# XL6009.net
KiCad netlist of a schematic drawn in Altium Designer
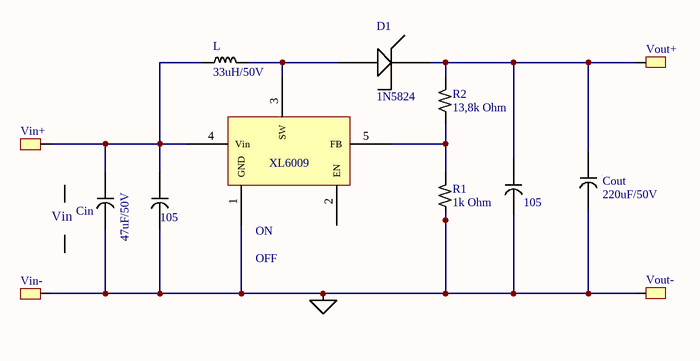
[diagram p0: XL6009.SchDoc]

(export (version "E")
  (design (tool "Eeschema 10.0.6"))
  (components
    (comp (ref "*") (value "Component_1") (libsource (lib "Schlib1") (part "Component_1")))
    (comp (ref "*1") (value "Component_2") (libsource (lib "Schlib1") (part "Component_2")))
    (comp (ref "*2") (value "Component_2") (libsource (lib "Schlib1") (part "Component_2")))
    (comp (ref "1") (value "105") (footprint "PCBComponent_1") (libsource (lib "Schlib1") (part "105")))
    (comp (ref "105") (value "105") (footprint "PCBComponent_1") (libsource (lib "Schlib1") (part "105")))
    (comp (ref "Cin")
      (value "47uF/50V")
      (footprint "Cout:PCBComponent_1")
      (libsource (lib "Schlib1") (part "capacitor"))
    )
    (comp (ref "Cout")
      (value "220uF/50V")
      (footprint "Cout:PCBComponent_1")
      (libsource (lib "Schlib1") (part "capacitor"))
    )
    (comp (ref "D1") (value "1N5824") (footprint "1N5824") (libsource (lib "Schlib1") (part "diode")))
    (comp (ref "L")
      (value "33uH/50V")
      (footprint "coil:PCBComponent_1")
      (libsource (lib "Schlib1") (part "Electrolytic Cap"))
    )
    (comp (ref "R1")
      (value "1k Ohm")
      (footprint "resistor0805:PCBComponent_1")
      (libsource (lib "Schlib1") (part "resistor"))
    )
    (comp (ref "R2")
      (value "13,8k Ohm")
      (footprint "resistor0805:PCBComponent_1")
      (libsource (lib "Schlib1") (part "resistor"))
    )
    (comp (ref "Vin+") (value "p1") (footprint "P1") (libsource (lib "Schlib1") (part "p1")))
    (comp (ref "Vin-") (value "p1") (footprint "P1") (libsource (lib "Schlib1") (part "p1")))
    (comp (ref "Vout+") (value "p1") (footprint "P1") (libsource (lib "") (part "p1_1")))
    (comp (ref "Vout-") (value "p1") (footprint "P1") (libsource (lib "") (part "p1_1")))
    (comp (ref "XL6009") (value "XL6009") (footprint "XL6009") (libsource (lib "Schlib1") (part "XL6009")))
  )
  (nets
    (net (code "1") (name "GND") (class "Default")
      (node (ref "1") (pin "2") (pinfunction "2_2") (pintype "passive"))
      (node (ref "105") (pin "2") (pinfunction "2_2") (pintype "passive"))
      (node (ref "Cin") (pin "2") (pinfunction "2_2") (pintype "passive"))
      (node (ref "Cout") (pin "2") (pinfunction "2_2") (pintype "passive"))
      (node (ref "R1") (pin "1") (pinfunction "1_1") (pintype "passive"))
      (node (ref "Vin-") (pin "21") (pinfunction "21_21") (pintype "passive"))
      (node (ref "Vout-") (pin "21") (pinfunction "21_21") (pintype "passive"))
      (node (ref "XL6009") (pin "1") (pinfunction "GND_1") (pintype "passive"))
    )
    (net (code "2") (name "Net-(1-Pad1)") (class "Default")
      (node (ref "1") (pin "1") (pinfunction "1_1") (pintype "passive"))
      (node (ref "Cout") (pin "1") (pinfunction "1_1") (pintype "passive"))
      (node (ref "D1") (pin "1") (pinfunction "1_1") (pintype "passive"))
      (node (ref "R2") (pin "2") (pinfunction "1_2") (pintype "passive"))
      (node (ref "Vout+") (pin "21") (pinfunction "21_21") (pintype "passive"))
    )
    (net (code "3") (name "Net-(XL6009-FB)") (class "Default")
      (node (ref "R1") (pin "2") (pinfunction "1_2") (pintype "passive"))
      (node (ref "R2") (pin "1") (pinfunction "1_1") (pintype "passive"))
      (node (ref "XL6009") (pin "5") (pinfunction "FB_5") (pintype "passive"))
    )
    (net (code "4") (name "Net-(XL6009-SW)") (class "Default")
      (node (ref "D1") (pin "2") (pinfunction "2_2") (pintype "passive"))
      (node (ref "L") (pin "2") (pinfunction "2_2") (pintype "passive"))
      (node (ref "XL6009") (pin "3") (pinfunction "SW_3") (pintype "passive"))
    )
    (net (code "5") (name "Net-(XL6009-Vin)") (class "Default")
      (node (ref "105") (pin "1") (pinfunction "1_1") (pintype "passive"))
      (node (ref "Cin") (pin "1") (pinfunction "1_1") (pintype "passive"))
      (node (ref "L") (pin "1") (pinfunction "1_1") (pintype "passive"))
      (node (ref "Vin+") (pin "21") (pinfunction "21_21") (pintype "passive"))
      (node (ref "XL6009") (pin "4") (pinfunction "Vin_4") (pintype "passive"))
    )
    (net (code "6") (name "unconnected-(XL6009-EN-Pad2)") (class "Default")
      (node (ref "XL6009") (pin "2") (pinfunction "EN_2") (pintype "passive"))
    )
  )
)
